# Fensterkontakt4.net
KiCad netlist of a schematic drawn in EAGLE
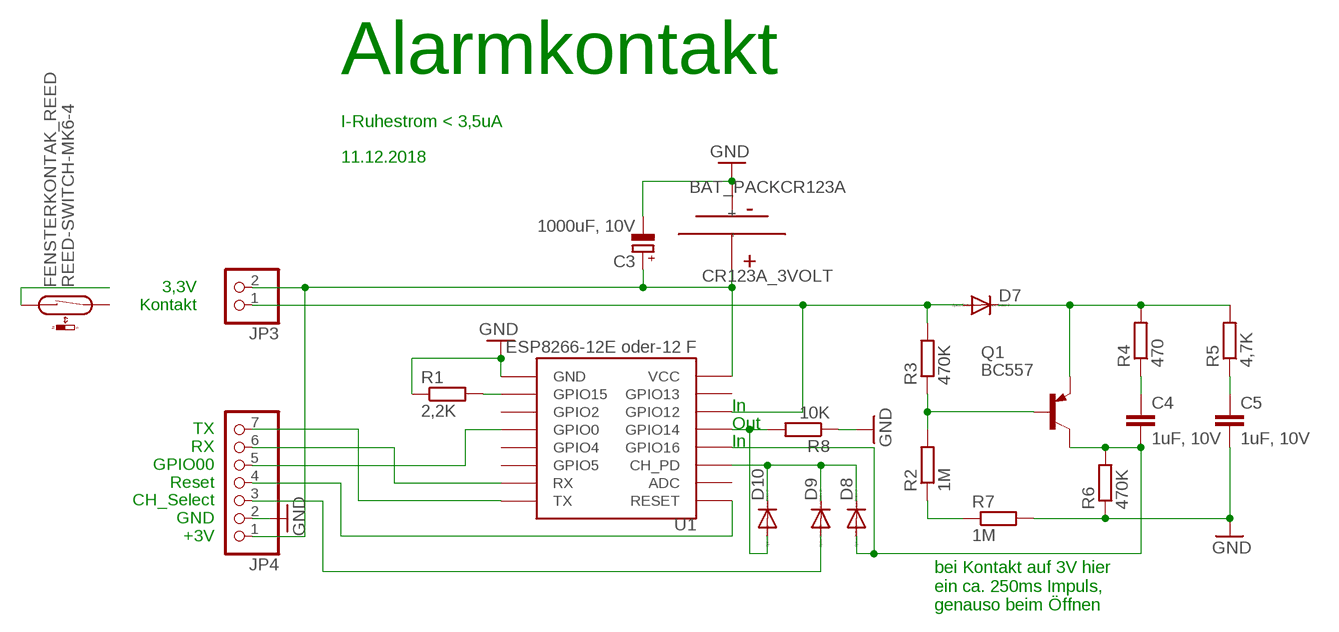
[diagram p0: schematic, sheet 1]

(export (version "E")
  (design (tool "Eeschema 10.0.6"))
  (components
    (comp (ref "C3")
      (value "1000uF, 10V")
      (footprint "eagle-import:E5-4")
      (libsource (lib "eagle-import") (part "CPOL-EUE5-4"))
    )
    (comp (ref "C4")
      (value "1uF, 10V")
      (footprint "eagle-import:C075-032X103")
      (libsource (lib "eagle-import") (part "C-EU075-032X103"))
    )
    (comp (ref "C5")
      (value "1uF, 10V")
      (footprint "eagle-import:C075-032X103")
      (libsource (lib "eagle-import") (part "C-EU075-032X103"))
    )
    (comp (ref "CR123A_3VOLT")
      (value "BAT_PACKCR123A")
      (footprint "eagle-import:BH123A")
      (fields (field (name "MANUFACTURER") "MPD") (field (name "MPN") "BH123A"))
      (libsource (lib "eagle-import") (part "BAT_PACKCR123A"))
    )
    (comp (ref "D7")
      (value "DIODE-D-7.5")
      (footprint "eagle-import:D-7.5")
      (libsource (lib "eagle-import") (part "DIODE-D-7.5"))
    )
    (comp (ref "D8")
      (value "DIODE-D-7.5")
      (footprint "eagle-import:D-7.5")
      (libsource (lib "eagle-import") (part "DIODE-D-7.5"))
    )
    (comp (ref "D9")
      (value "DIODE-D-7.5")
      (footprint "eagle-import:D-7.5")
      (libsource (lib "eagle-import") (part "DIODE-D-7.5"))
    )
    (comp (ref "D10")
      (value "DIODE-D-7.5")
      (footprint "eagle-import:D-7.5")
      (libsource (lib "eagle-import") (part "DIODE-D-7.5"))
    )
    (comp (ref "FENSTERKONTAK_REED")
      (value "REED-SWITCH-MK6-4")
      (footprint "eagle-import:MK6-4")
      (libsource (lib "eagle-import") (part "REED-SWITCH-MK6-4"))
    )
    (comp (ref "JP3")
      (value "PINHD-1X2")
      (footprint "eagle-import:1X02")
      (libsource (lib "eagle-import") (part "PINHD-1X2"))
    )
    (comp (ref "JP4")
      (value "PINHD-1X7")
      (footprint "eagle-import:1X07")
      (libsource (lib "eagle-import") (part "PINHD-1X7"))
    )
    (comp (ref "Q1")
      (value "BC557")
      (footprint "eagle-import:TO92-EBC")
      (libsource (lib "eagle-import") (part "BC557"))
    )
    (comp (ref "R1")
      (value "2,2K")
      (footprint "eagle-import:0207_7")
      (libsource (lib "eagle-import") (part "R-EU_0207/7"))
    )
    (comp (ref "R2")
      (value "1M")
      (footprint "eagle-import:0207_7")
      (libsource (lib "eagle-import") (part "R-EU_0207/7"))
    )
    (comp (ref "R3")
      (value "470K")
      (footprint "eagle-import:0207_7")
      (libsource (lib "eagle-import") (part "R-EU_0207/7"))
    )
    (comp (ref "R4")
      (value "470")
      (footprint "eagle-import:0207_7")
      (libsource (lib "eagle-import") (part "R-EU_0207/7"))
    )
    (comp (ref "R5")
      (value "4,7K")
      (footprint "eagle-import:0207_7")
      (libsource (lib "eagle-import") (part "R-EU_0207/7"))
    )
    (comp (ref "R6")
      (value "470K")
      (footprint "eagle-import:0207_7")
      (libsource (lib "eagle-import") (part "R-EU_0207/7"))
    )
    (comp (ref "R7")
      (value "1M")
      (footprint "eagle-import:0207_7")
      (libsource (lib "eagle-import") (part "R-EU_0207/7"))
    )
    (comp (ref "R8")
      (value "10K")
      (footprint "eagle-import:0207_7")
      (libsource (lib "eagle-import") (part "R-EU_0207/7"))
    )
    (comp (ref "U1")
      (value "ESP8266-12E oder-12 F")
      (footprint "eagle-import:ESP12")
      (libsource (lib "eagle-import") (part "ESP12"))
    )
  )
  (nets
    (net (code "1") (name "GND") (class "Default")
      (node (ref "C3") (pin "-") (pinfunction "-_-") (pintype "passive"))
      (node (ref "C5") (pin "2") (pinfunction "2_2") (pintype "passive"))
      (node (ref "CR123A_3VOLT") (pin "-") (pinfunction "-_-") (pintype "bidirectional"))
      (node (ref "JP4") (pin "2") (pinfunction "2_2") (pintype "passive"))
      (node (ref "R1") (pin "1") (pinfunction "1_1") (pintype "passive"))
      (node (ref "R6") (pin "1") (pinfunction "1_1") (pintype "passive"))
      (node (ref "R7") (pin "2") (pinfunction "2_2") (pintype "passive"))
      (node (ref "R8") (pin "1") (pinfunction "1_1") (pintype "passive"))
      (node (ref "U1") (pin "GND") (pinfunction "GND_GND") (pintype "bidirectional"))
    )
    (net (code "2") (name "Net-(C3-Pad+)") (class "Default")
      (node (ref "C3") (pin "+") (pinfunction "+_+") (pintype "passive"))
      (node (ref "CR123A_3VOLT") (pin "+") (pinfunction "+_+") (pintype "bidirectional"))
      (node (ref "JP3") (pin "2") (pinfunction "2_2") (pintype "passive"))
      (node (ref "JP4") (pin "1") (pinfunction "1_1") (pintype "passive"))
      (node (ref "U1") (pin "VCC") (pinfunction "VCC_VCC") (pintype "bidirectional"))
    )
    (net (code "3") (name "Net-(C4-Pad1)") (class "Default")
      (node (ref "C4") (pin "1") (pinfunction "1_1") (pintype "passive"))
      (node (ref "R4") (pin "1") (pinfunction "1_1") (pintype "passive"))
    )
    (net (code "4") (name "Net-(C4-Pad2)") (class "Default")
      (node (ref "C4") (pin "2") (pinfunction "2_2") (pintype "passive"))
      (node (ref "D8") (pin "A") (pinfunction "A_A") (pintype "passive"))
      (node (ref "Q1") (pin "C") (pinfunction "C_C") (pintype "passive"))
      (node (ref "R6") (pin "2") (pinfunction "2_2") (pintype "passive"))
      (node (ref "U1") (pin "GPIO16") (pinfunction "GPIO16_GPIO16") (pintype "bidirectional"))
    )
    (net (code "5") (name "Net-(C5-Pad1)") (class "Default")
      (node (ref "C5") (pin "1") (pinfunction "1_1") (pintype "passive"))
      (node (ref "R5") (pin "1") (pinfunction "1_1") (pintype "passive"))
    )
    (net (code "6") (name "Net-(D7-PadA)") (class "Default")
      (node (ref "D7") (pin "A") (pinfunction "A_A") (pintype "passive"))
      (node (ref "JP3") (pin "1") (pinfunction "1_1") (pintype "passive"))
      (node (ref "R3") (pin "2") (pinfunction "2_2") (pintype "passive"))
      (node (ref "U1") (pin "GPIO12") (pinfunction "GPIO12_GPIO12") (pintype "bidirectional"))
    )
    (net (code "7") (name "Net-(D7-PadC)") (class "Default")
      (node (ref "D7") (pin "C") (pinfunction "C_C") (pintype "passive"))
      (node (ref "Q1") (pin "E") (pinfunction "E_E") (pintype "passive"))
      (node (ref "R4") (pin "2") (pinfunction "2_2") (pintype "passive"))
      (node (ref "R5") (pin "2") (pinfunction "2_2") (pintype "passive"))
    )
    (net (code "8") (name "Net-(D9-PadA)") (class "Default")
      (node (ref "D9") (pin "A") (pinfunction "A_A") (pintype "passive"))
      (node (ref "JP4") (pin "3") (pinfunction "3_3") (pintype "passive"))
    )
    (net (code "9") (name "Net-(D10-PadA)") (class "Default")
      (node (ref "D10") (pin "A") (pinfunction "A_A") (pintype "passive"))
      (node (ref "R8") (pin "2") (pinfunction "2_2") (pintype "passive"))
      (node (ref "U1") (pin "GPIO14") (pinfunction "GPIO14_GPIO14") (pintype "bidirectional"))
    )
    (net (code "10") (name "Net-(D10-PadC)") (class "Default")
      (node (ref "D10") (pin "C") (pinfunction "C_C") (pintype "passive"))
      (node (ref "D8") (pin "C") (pinfunction "C_C") (pintype "passive"))
      (node (ref "D9") (pin "C") (pinfunction "C_C") (pintype "passive"))
      (node (ref "U1") (pin "CH_PD") (pinfunction "CH_PD_CH_PD") (pintype "bidirectional"))
    )
    (net (code "11") (name "Net-(JP4-Pad4)") (class "Default")
      (node (ref "JP4") (pin "4") (pinfunction "4_4") (pintype "passive"))
      (node (ref "U1") (pin "RESET") (pinfunction "RESET_RESET") (pintype "bidirectional"))
    )
    (net (code "12") (name "Net-(JP4-Pad5)") (class "Default")
      (node (ref "JP4") (pin "5") (pinfunction "5_5") (pintype "passive"))
      (node (ref "U1") (pin "GPIO0") (pinfunction "GPIO0_GPIO0") (pintype "bidirectional"))
    )
    (net (code "13") (name "Net-(JP4-Pad6)") (class "Default")
      (node (ref "JP4") (pin "6") (pinfunction "6_6") (pintype "passive"))
      (node (ref "U1") (pin "RX") (pinfunction "RX_RX") (pintype "bidirectional"))
    )
    (net (code "14") (name "Net-(JP4-Pad7)") (class "Default")
      (node (ref "JP4") (pin "7") (pinfunction "7_7") (pintype "passive"))
      (node (ref "U1") (pin "TX") (pinfunction "TX_TX") (pintype "bidirectional"))
    )
    (net (code "15") (name "Net-(Q1-PadB)") (class "Default")
      (node (ref "Q1") (pin "B") (pinfunction "B_B") (pintype "passive"))
      (node (ref "R2") (pin "2") (pinfunction "2_2") (pintype "passive"))
      (node (ref "R3") (pin "1") (pinfunction "1_1") (pintype "passive"))
    )
    (net (code "16") (name "Net-(R1-Pad2)") (class "Default")
      (node (ref "R1") (pin "2") (pinfunction "2_2") (pintype "passive"))
      (node (ref "U1") (pin "GPIO15") (pinfunction "GPIO15_GPIO15") (pintype "bidirectional"))
    )
    (net (code "17") (name "Net-(R2-Pad1)") (class "Default")
      (node (ref "R2") (pin "1") (pinfunction "1_1") (pintype "passive"))
      (node (ref "R7") (pin "1") (pinfunction "1_1") (pintype "passive"))
    )
    (net (code "18") (name "unconnected-(FENSTERKONTAK_REED-Pad1)") (class "Default")
      (node (ref "FENSTERKONTAK_REED") (pin "1") (pinfunction "1_1") (pintype "passive"))
    )
    (net (code "19") (name "unconnected-(FENSTERKONTAK_REED-Pad2)") (class "Default")
      (node (ref "FENSTERKONTAK_REED") (pin "2") (pinfunction "2_2") (pintype "passive"))
    )
    (net (code "20") (name "unconnected-(U1-PadADC)") (class "Default")
      (node (ref "U1") (pin "ADC") (pinfunction "ADC_ADC") (pintype "bidirectional"))
    )
    (net (code "21") (name "unconnected-(U1-PadGPIO2)") (class "Default")
      (node (ref "U1") (pin "GPIO2") (pinfunction "GPIO2_GPIO2") (pintype "bidirectional"))
    )
    (net (code "22") (name "unconnected-(U1-PadGPIO4)") (class "Default")
      (node (ref "U1") (pin "GPIO4") (pinfunction "GPIO4_GPIO4") (pintype "bidirectional"))
    )
    (net (code "23") (name "unconnected-(U1-PadGPIO5)") (class "Default")
      (node (ref "U1") (pin "GPIO5") (pinfunction "GPIO5_GPIO5") (pintype "bidirectional"))
    )
    (net (code "24") (name "unconnected-(U1-PadGPIO13)") (class "Default")
      (node (ref "U1") (pin "GPIO13") (pinfunction "GPIO13_GPIO13") (pintype "bidirectional"))
    )
  )
)
